# I2C_switch.net
KiCad netlist of a schematic drawn in Altium Designer
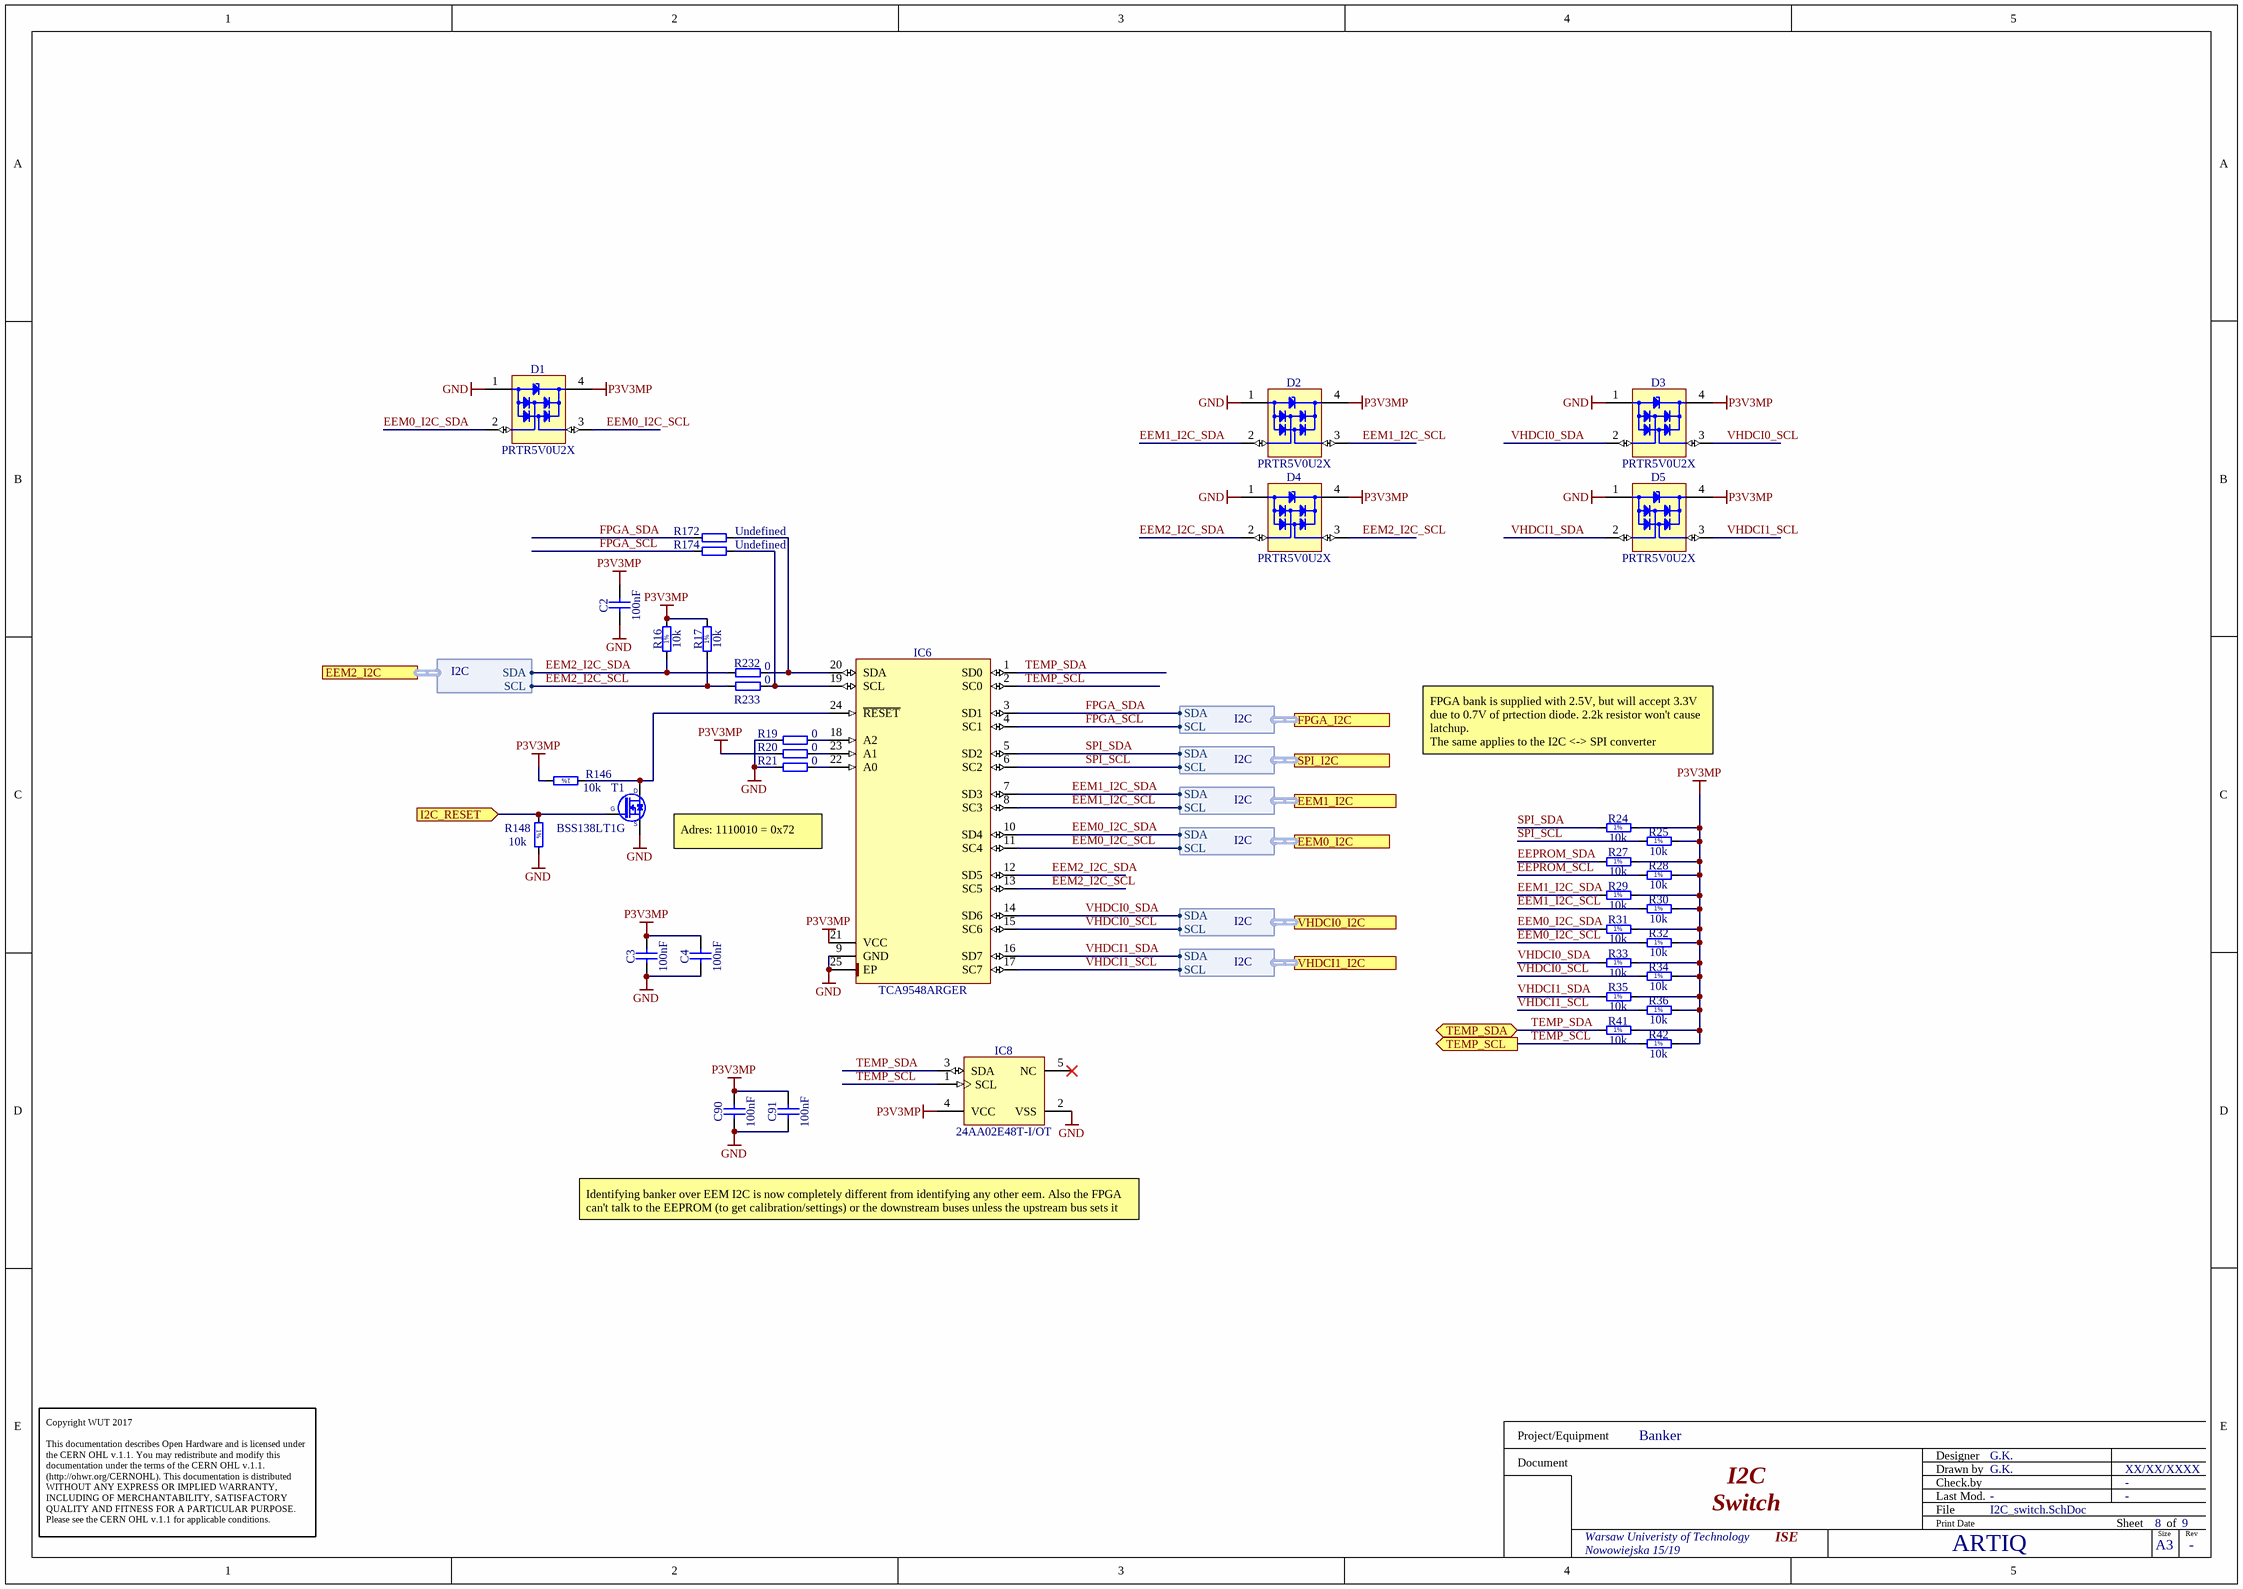
[diagram p0: I2C_switch.SchDoc]

(export (version "E")
  (design (tool "Eeschema 10.0.6"))
  (components
    (comp (ref "C2")
      (value "100nF")
      (footprint "CAPC1005X55N")
      (description "Non-polarised capacitor")
      (fields
        (field (name "PART NUMBER") "CC0402_100NF_16V_10%_X5R")
        (field (name "VOLTAGE") "16V")
        (field (name "AUTHOR") "CERN DEM JLC")
      )
      (libsource (lib "Capacitors") (part "Capacitor - non polarized"))
    )
    (comp (ref "C3")
      (value "100nF")
      (footprint "CAPC1005X55N")
      (description "Non-polarised capacitor")
      (fields
        (field (name "PART NUMBER") "CC0402_100NF_16V_10%_X5R")
        (field (name "VOLTAGE") "16V")
        (field (name "AUTHOR") "CERN DEM JLC")
      )
      (libsource (lib "Capacitors") (part "Capacitor - non polarized"))
    )
    (comp (ref "C4")
      (value "100nF")
      (footprint "CAPC1005X55N")
      (description "Non-polarised capacitor")
      (fields
        (field (name "PART NUMBER") "CC0402_100NF_16V_10%_X5R")
        (field (name "VOLTAGE") "16V")
        (field (name "AUTHOR") "CERN DEM JLC")
      )
      (libsource (lib "Capacitors") (part "Capacitor - non polarized"))
    )
    (comp (ref "C90")
      (value "100nF")
      (footprint "CAPC1005X55N")
      (description "Non-polarised capacitor")
      (fields
        (field (name "PART NUMBER") "CC0402_100NF_16V_10%_X5R")
        (field (name "VOLTAGE") "16V")
        (field (name "AUTHOR") "CERN DEM JLC")
      )
      (libsource (lib "Capacitors") (part "Capacitor - non polarized"))
    )
    (comp (ref "C91")
      (value "100nF")
      (footprint "CAPC1005X55N")
      (description "Non-polarised capacitor")
      (fields
        (field (name "PART NUMBER") "CC0402_100NF_16V_10%_X5R")
        (field (name "VOLTAGE") "16V")
        (field (name "AUTHOR") "CERN DEM JLC")
      )
      (libsource (lib "Capacitors") (part "Capacitor - non polarized"))
    )
    (comp (ref "D1")
      (value "PRTR5V0U2X")
      (footprint "SOT190P230X110-4N")
      (description "Ultra Low Capacitance Double Rail-to-Rail ESD Protection Diode")
      (fields
        (field (name "VOLTAGE") "5.5V")
        (field (name "MANUFACTURER") "NXP SEMICONDUCTORS")
        (field (name "AUTHOR") "CERN DEM JLC")
      )
      (libsource (lib "ICs And Semiconductors") (part "PRTR5V0U2X"))
    )
    (comp (ref "D2")
      (value "PRTR5V0U2X")
      (footprint "SOT190P230X110-4N")
      (description "Ultra Low Capacitance Double Rail-to-Rail ESD Protection Diode")
      (fields
        (field (name "VOLTAGE") "5.5V")
        (field (name "MANUFACTURER") "NXP SEMICONDUCTORS")
        (field (name "AUTHOR") "CERN DEM JLC")
      )
      (libsource (lib "ICs And Semiconductors") (part "PRTR5V0U2X"))
    )
    (comp (ref "D3")
      (value "PRTR5V0U2X")
      (footprint "SOT190P230X110-4N")
      (description "Ultra Low Capacitance Double Rail-to-Rail ESD Protection Diode")
      (fields
        (field (name "VOLTAGE") "5.5V")
        (field (name "MANUFACTURER") "NXP SEMICONDUCTORS")
        (field (name "AUTHOR") "CERN DEM JLC")
      )
      (libsource (lib "ICs And Semiconductors") (part "PRTR5V0U2X"))
    )
    (comp (ref "D4")
      (value "PRTR5V0U2X")
      (footprint "SOT190P230X110-4N")
      (description "Ultra Low Capacitance Double Rail-to-Rail ESD Protection Diode")
      (fields
        (field (name "VOLTAGE") "5.5V")
        (field (name "MANUFACTURER") "NXP SEMICONDUCTORS")
        (field (name "AUTHOR") "CERN DEM JLC")
      )
      (libsource (lib "ICs And Semiconductors") (part "PRTR5V0U2X"))
    )
    (comp (ref "D5")
      (value "PRTR5V0U2X")
      (footprint "SOT190P230X110-4N")
      (description "Ultra Low Capacitance Double Rail-to-Rail ESD Protection Diode")
      (fields
        (field (name "VOLTAGE") "5.5V")
        (field (name "MANUFACTURER") "NXP SEMICONDUCTORS")
        (field (name "AUTHOR") "CERN DEM JLC")
      )
      (libsource (lib "ICs And Semiconductors") (part "PRTR5V0U2X"))
    )
    (comp (ref "IC6")
      (value "TCA9548ARGER")
      (footprint "QFN50P400X400X100-25N-S220")
      (description "Low Voltage 8-Channel I2C Switch With Reset")
      (fields (field (name "MANUFACTURER") "TEXAS INSTRUMENTS") (field (name "AUTHOR") "CERN DEM JLC"))
      (libsource (lib "ICs And Semiconductors") (part "TCA9548ARGER"))
    )
    (comp (ref "IC8")
      (value "24AA02E48T-I/OT")
      (footprint "SOT95P280X145-5N")
      (description "1.7V-5.5V, 2K I2C Serial EEPROM With EUI-48 Node Identity")
      (fields (field (name "MANUFACTURER") "MICROCHIP TECHNOLOGY") (field (name "AUTHOR") "CERN DEM MR"))
      (libsource (lib "ICs And Semiconductors") (part "24AA02E48T-I/OT"))
    )
    (comp (ref "R16")
      (value "10k")
      (footprint "RESC1005X40N")
      (description "Resistor - 1%")
      (fields
        (field (name "PART NUMBER") "R0402_10K_1%_0.0625W_100PPM")
        (field (name "POWER") "0.0625W")
        (field (name "AUTHOR") "CERN DEM JLC")
      )
      (libsource (lib "Resistors") (part "Resistor - 1%"))
    )
    (comp (ref "R17")
      (value "10k")
      (footprint "RESC1005X40N")
      (description "Resistor - 1%")
      (fields
        (field (name "PART NUMBER") "R0402_10K_1%_0.0625W_100PPM")
        (field (name "POWER") "0.0625W")
        (field (name "AUTHOR") "CERN DEM JLC")
      )
      (libsource (lib "Resistors") (part "Resistor - 1%"))
    )
    (comp (ref "R19")
      (value "0")
      (footprint "RESC1005X40N")
      (description "Resistor")
      (fields
        (field (name "PART NUMBER") "R0402_0R_JUMPER")
        (field (name "MANUFACTURER") "GENERIC")
        (field (name "AUTHOR") "CERN DEM JLC")
      )
      (libsource (lib "Resistors") (part "Resistor"))
    )
    (comp (ref "R20")
      (value "0")
      (footprint "RESC1005X40N")
      (description "Resistor")
      (fields
        (field (name "PART NUMBER") "R0402_0R_JUMPER")
        (field (name "MANUFACTURER") "GENERIC")
        (field (name "AUTHOR") "CERN DEM JLC")
      )
      (libsource (lib "Resistors") (part "Resistor"))
    )
    (comp (ref "R21")
      (value "0")
      (footprint "RESC1005X40N")
      (description "Resistor")
      (fields
        (field (name "PART NUMBER") "R0402_0R_JUMPER")
        (field (name "MANUFACTURER") "GENERIC")
        (field (name "AUTHOR") "CERN DEM JLC")
      )
      (libsource (lib "Resistors") (part "Resistor"))
    )
    (comp (ref "R24")
      (value "10k")
      (footprint "RESC1005X40N")
      (description "Resistor - 1%")
      (fields
        (field (name "PART NUMBER") "R0402_10K_1%_0.0625W_100PPM")
        (field (name "POWER") "0.0625W")
        (field (name "AUTHOR") "CERN DEM JLC")
      )
      (libsource (lib "Resistors") (part "Resistor - 1%"))
    )
    (comp (ref "R25")
      (value "10k")
      (footprint "RESC1005X40N")
      (description "Resistor - 1%")
      (fields
        (field (name "PART NUMBER") "R0402_10K_1%_0.0625W_100PPM")
        (field (name "POWER") "0.0625W")
        (field (name "AUTHOR") "CERN DEM JLC")
      )
      (libsource (lib "Resistors") (part "Resistor - 1%"))
    )
    (comp (ref "R27")
      (value "10k")
      (footprint "RESC1005X40N")
      (description "Resistor - 1%")
      (fields
        (field (name "PART NUMBER") "R0402_10K_1%_0.0625W_100PPM")
        (field (name "POWER") "0.0625W")
        (field (name "AUTHOR") "CERN DEM JLC")
      )
      (libsource (lib "Resistors") (part "Resistor - 1%"))
    )
    (comp (ref "R28")
      (value "10k")
      (footprint "RESC1005X40N")
      (description "Resistor - 1%")
      (fields
        (field (name "PART NUMBER") "R0402_10K_1%_0.0625W_100PPM")
        (field (name "POWER") "0.0625W")
        (field (name "AUTHOR") "CERN DEM JLC")
      )
      (libsource (lib "Resistors") (part "Resistor - 1%"))
    )
    (comp (ref "R29")
      (value "10k")
      (footprint "RESC1005X40N")
      (description "Resistor - 1%")
      (fields
        (field (name "PART NUMBER") "R0402_10K_1%_0.0625W_100PPM")
        (field (name "POWER") "0.0625W")
        (field (name "AUTHOR") "CERN DEM JLC")
      )
      (libsource (lib "Resistors") (part "Resistor - 1%"))
    )
    (comp (ref "R30")
      (value "10k")
      (footprint "RESC1005X40N")
      (description "Resistor - 1%")
      (fields
        (field (name "PART NUMBER") "R0402_10K_1%_0.0625W_100PPM")
        (field (name "POWER") "0.0625W")
        (field (name "AUTHOR") "CERN DEM JLC")
      )
      (libsource (lib "Resistors") (part "Resistor - 1%"))
    )
    (comp (ref "R31")
      (value "10k")
      (footprint "RESC1005X40N")
      (description "Resistor - 1%")
      (fields
        (field (name "PART NUMBER") "R0402_10K_1%_0.0625W_100PPM")
        (field (name "POWER") "0.0625W")
        (field (name "AUTHOR") "CERN DEM JLC")
      )
      (libsource (lib "Resistors") (part "Resistor - 1%"))
    )
    (comp (ref "R32")
      (value "10k")
      (footprint "RESC1005X40N")
      (description "Resistor - 1%")
      (fields
        (field (name "PART NUMBER") "R0402_10K_1%_0.0625W_100PPM")
        (field (name "POWER") "0.0625W")
        (field (name "AUTHOR") "CERN DEM JLC")
      )
      (libsource (lib "Resistors") (part "Resistor - 1%"))
    )
    (comp (ref "R33")
      (value "10k")
      (footprint "RESC1005X40N")
      (description "Resistor - 1%")
      (fields
        (field (name "PART NUMBER") "R0402_10K_1%_0.0625W_100PPM")
        (field (name "POWER") "0.0625W")
        (field (name "AUTHOR") "CERN DEM JLC")
      )
      (libsource (lib "Resistors") (part "Resistor - 1%"))
    )
    (comp (ref "R34")
      (value "10k")
      (footprint "RESC1005X40N")
      (description "Resistor - 1%")
      (fields
        (field (name "PART NUMBER") "R0402_10K_1%_0.0625W_100PPM")
        (field (name "POWER") "0.0625W")
        (field (name "AUTHOR") "CERN DEM JLC")
      )
      (libsource (lib "Resistors") (part "Resistor - 1%"))
    )
    (comp (ref "R35")
      (value "10k")
      (footprint "RESC1005X40N")
      (description "Resistor - 1%")
      (fields
        (field (name "PART NUMBER") "R0402_10K_1%_0.0625W_100PPM")
        (field (name "POWER") "0.0625W")
        (field (name "AUTHOR") "CERN DEM JLC")
      )
      (libsource (lib "Resistors") (part "Resistor - 1%"))
    )
    (comp (ref "R36")
      (value "10k")
      (footprint "RESC1005X40N")
      (description "Resistor - 1%")
      (fields
        (field (name "PART NUMBER") "R0402_10K_1%_0.0625W_100PPM")
        (field (name "POWER") "0.0625W")
        (field (name "AUTHOR") "CERN DEM JLC")
      )
      (libsource (lib "Resistors") (part "Resistor - 1%"))
    )
    (comp (ref "R41")
      (value "10k")
      (footprint "RESC1005X40N")
      (description "Resistor - 1%")
      (fields
        (field (name "PART NUMBER") "R0402_10K_1%_0.0625W_100PPM")
        (field (name "POWER") "0.0625W")
        (field (name "AUTHOR") "CERN DEM JLC")
      )
      (libsource (lib "Resistors") (part "Resistor - 1%"))
    )
    (comp (ref "R42")
      (value "10k")
      (footprint "RESC1005X40N")
      (description "Resistor - 1%")
      (fields
        (field (name "PART NUMBER") "R0402_10K_1%_0.0625W_100PPM")
        (field (name "POWER") "0.0625W")
        (field (name "AUTHOR") "CERN DEM JLC")
      )
      (libsource (lib "Resistors") (part "Resistor - 1%"))
    )
    (comp (ref "R146")
      (value "10k")
      (footprint "RESC1005X40N")
      (description "Resistor - 1%")
      (fields
        (field (name "PART NUMBER") "R0402_10K_1%_0.0625W_100PPM")
        (field (name "POWER") "0.0625W")
        (field (name "AUTHOR") "CERN DEM JLC")
      )
      (libsource (lib "Resistors") (part "Resistor - 1%"))
    )
    (comp (ref "R148")
      (value "10k")
      (footprint "RESC1005X40N")
      (description "Resistor - 1%")
      (fields
        (field (name "PART NUMBER") "R0402_10K_1%_0.0625W_100PPM")
        (field (name "POWER") "0.0625W")
        (field (name "AUTHOR") "CERN DEM JLC")
      )
      (libsource (lib "Resistors") (part "Resistor - 1%"))
    )
    (comp (ref "R172")
      (value "Undefined")
      (footprint "RESC1608X55N")
      (description "Resistor")
      (fields (field (name "PART NUMBER") "R0603_NO-VALUE") (field (name "AUTHOR") "CERN DEM JLC"))
      (libsource (lib "Resistors") (part "Resistor"))
    )
    (comp (ref "R174")
      (value "Undefined")
      (footprint "RESC1608X55N")
      (description "Resistor")
      (fields (field (name "PART NUMBER") "R0603_NO-VALUE") (field (name "AUTHOR") "CERN DEM JLC"))
      (libsource (lib "Resistors") (part "Resistor"))
    )
    (comp (ref "R232")
      (value "0")
      (footprint "RESC1608X55N")
      (description "Resistor")
      (fields
        (field (name "PART NUMBER") "R0603_0R_JUMPER")
        (field (name "MANUFACTURER") "GENERIC")
        (field (name "AUTHOR") "CERN DEM JLC")
      )
      (libsource (lib "Resistors") (part "Resistor"))
    )
    (comp (ref "R233")
      (value "0")
      (footprint "RESC1608X55N")
      (description "Resistor")
      (fields
        (field (name "PART NUMBER") "R0603_0R_JUMPER")
        (field (name "MANUFACTURER") "GENERIC")
        (field (name "AUTHOR") "CERN DEM JLC")
      )
      (libsource (lib "Resistors") (part "Resistor"))
    )
    (comp (ref "T1")
      (value "BSS138LT1G")
      (footprint "SOT95P240X110-3N")
      (description "N-CHANNEL MOSFET WITH DIODE")
      (fields (field (name "MANUFACTURER") "ON SEMICONDUCTOR") (field (name "AUTHOR") "CERN DEM JLC"))
      (libsource (lib "ICs And Semiconductors") (part "N-MOSFET-D 1G 2S 3D"))
    )
  )
  (nets
    (net (code "2") (name "/EEM0_I2C_SCL") (class "Default")
      (node (ref "D1") (pin "3") (pinfunction "I/O2_3") (pintype "bidirectional"))
      (node (ref "IC6") (pin "11") (pinfunction "SC4_11") (pintype "bidirectional"))
      (node (ref "R32") (pin "1") (pinfunction "1_1") (pintype "passive"))
    )
    (net (code "3") (name "/EEM0_I2C_SDA") (class "Default")
      (node (ref "D1") (pin "2") (pinfunction "I/O1_2") (pintype "bidirectional"))
      (node (ref "IC6") (pin "10") (pinfunction "SD4_10") (pintype "bidirectional"))
      (node (ref "R31") (pin "1") (pinfunction "1_1") (pintype "passive"))
    )
    (net (code "4") (name "/EEM1_I2C_SCL") (class "Default")
      (node (ref "D2") (pin "3") (pinfunction "I/O2_3") (pintype "bidirectional"))
      (node (ref "IC6") (pin "8") (pinfunction "SC3_8") (pintype "bidirectional"))
      (node (ref "R30") (pin "1") (pinfunction "1_1") (pintype "passive"))
    )
    (net (code "5") (name "/EEM1_I2C_SDA") (class "Default")
      (node (ref "D2") (pin "2") (pinfunction "I/O1_2") (pintype "bidirectional"))
      (node (ref "IC6") (pin "7") (pinfunction "SD3_7") (pintype "bidirectional"))
      (node (ref "R29") (pin "1") (pinfunction "1_1") (pintype "passive"))
    )
    (net (code "6") (name "/EEM2_I2C_SCL") (class "Default")
      (node (ref "D4") (pin "3") (pinfunction "I/O2_3") (pintype "bidirectional"))
      (node (ref "IC6") (pin "13") (pinfunction "SC5_13") (pintype "bidirectional"))
      (node (ref "R17") (pin "1") (pinfunction "1_1") (pintype "passive"))
      (node (ref "R233") (pin "1") (pinfunction "1_1") (pintype "passive"))
    )
    (net (code "7") (name "/EEM2_I2C_SDA") (class "Default")
      (node (ref "D4") (pin "2") (pinfunction "I/O1_2") (pintype "bidirectional"))
      (node (ref "IC6") (pin "12") (pinfunction "SD5_12") (pintype "bidirectional"))
      (node (ref "R16") (pin "1") (pinfunction "1_1") (pintype "passive"))
      (node (ref "R232") (pin "1") (pinfunction "1_1") (pintype "passive"))
    )
    (net (code "8") (name "/EEPROM_SCL") (class "Default")
      (node (ref "R28") (pin "1") (pinfunction "1_1") (pintype "passive"))
    )
    (net (code "9") (name "/EEPROM_SDA") (class "Default")
      (node (ref "R27") (pin "1") (pinfunction "1_1") (pintype "passive"))
    )
    (net (code "10") (name "/FPGA_SCL") (class "Default")
      (node (ref "IC6") (pin "4") (pinfunction "SC1_4") (pintype "bidirectional"))
      (node (ref "R174") (pin "1") (pinfunction "1_1") (pintype "passive"))
    )
    (net (code "11") (name "/FPGA_SDA") (class "Default")
      (node (ref "IC6") (pin "3") (pinfunction "SD1_3") (pintype "bidirectional"))
      (node (ref "R172") (pin "1") (pinfunction "1_1") (pintype "passive"))
    )
    (net (code "12") (name "/I2C_RESET") (class "Default")
      (node (ref "R148") (pin "1") (pinfunction "1_1") (pintype "passive"))
      (node (ref "T1") (pin "1") (pinfunction "G_1") (pintype "passive"))
    )
    (net (code "13") (name "/SPI_SCL") (class "Default")
      (node (ref "IC6") (pin "6") (pinfunction "SC2_6") (pintype "bidirectional"))
      (node (ref "R25") (pin "1") (pinfunction "1_1") (pintype "passive"))
    )
    (net (code "14") (name "/SPI_SDA") (class "Default")
      (node (ref "IC6") (pin "5") (pinfunction "SD2_5") (pintype "bidirectional"))
      (node (ref "R24") (pin "1") (pinfunction "1_1") (pintype "passive"))
    )
    (net (code "15") (name "/TEMP_SCL") (class "Default")
      (node (ref "IC6") (pin "2") (pinfunction "SC0_2") (pintype "bidirectional"))
      (node (ref "IC8") (pin "1") (pinfunction "SCL_1") (pintype "input"))
      (node (ref "R42") (pin "1") (pinfunction "1_1") (pintype "passive"))
    )
    (net (code "16") (name "/TEMP_SDA") (class "Default")
      (node (ref "IC6") (pin "1") (pinfunction "SD0_1") (pintype "bidirectional"))
      (node (ref "IC8") (pin "3") (pinfunction "SDA_3") (pintype "bidirectional"))
      (node (ref "R41") (pin "1") (pinfunction "1_1") (pintype "passive"))
    )
    (net (code "17") (name "/VHDCI0_SCL") (class "Default")
      (node (ref "D3") (pin "3") (pinfunction "I/O2_3") (pintype "bidirectional"))
      (node (ref "IC6") (pin "15") (pinfunction "SC6_15") (pintype "bidirectional"))
      (node (ref "R34") (pin "1") (pinfunction "1_1") (pintype "passive"))
    )
    (net (code "18") (name "/VHDCI0_SDA") (class "Default")
      (node (ref "D3") (pin "2") (pinfunction "I/O1_2") (pintype "bidirectional"))
      (node (ref "IC6") (pin "14") (pinfunction "SD6_14") (pintype "bidirectional"))
      (node (ref "R33") (pin "1") (pinfunction "1_1") (pintype "passive"))
    )
    (net (code "19") (name "/VHDCI1_SCL") (class "Default")
      (node (ref "D5") (pin "3") (pinfunction "I/O2_3") (pintype "bidirectional"))
      (node (ref "IC6") (pin "17") (pinfunction "SC7_17") (pintype "bidirectional"))
      (node (ref "R36") (pin "1") (pinfunction "1_1") (pintype "passive"))
    )
    (net (code "20") (name "/VHDCI1_SDA") (class "Default")
      (node (ref "D5") (pin "2") (pinfunction "I/O1_2") (pintype "bidirectional"))
      (node (ref "IC6") (pin "16") (pinfunction "SD7_16") (pintype "bidirectional"))
      (node (ref "R35") (pin "1") (pinfunction "1_1") (pintype "passive"))
    )
    (net (code "22") (name "GND") (class "Default")
      (node (ref "C2") (pin "1") (pinfunction "1_1") (pintype "passive"))
      (node (ref "C3") (pin "1") (pinfunction "1_1") (pintype "passive"))
      (node (ref "C4") (pin "1") (pinfunction "1_1") (pintype "passive"))
      (node (ref "C90") (pin "1") (pinfunction "1_1") (pintype "passive"))
      (node (ref "C91") (pin "1") (pinfunction "1_1") (pintype "passive"))
      (node (ref "D1") (pin "1") (pinfunction "GND_1") (pintype "power_in"))
      (node (ref "D2") (pin "1") (pinfunction "GND_1") (pintype "power_in"))
      (node (ref "D3") (pin "1") (pinfunction "GND_1") (pintype "power_in"))
      (node (ref "D4") (pin "1") (pinfunction "GND_1") (pintype "power_in"))
      (node (ref "D5") (pin "1") (pinfunction "GND_1") (pintype "power_in"))
      (node (ref "IC6") (pin "25") (pinfunction "EP_25") (pintype "power_in"))
      (node (ref "IC6") (pin "9") (pinfunction "GND_9") (pintype "power_in"))
      (node (ref "IC8") (pin "2") (pinfunction "VSS_2") (pintype "power_in"))
      (node (ref "R148") (pin "2") (pinfunction "2_2") (pintype "passive"))
      (node (ref "R19") (pin "1") (pinfunction "1_1") (pintype "passive"))
      (node (ref "R21") (pin "1") (pinfunction "1_1") (pintype "passive"))
      (node (ref "T1") (pin "2") (pinfunction "S_2") (pintype "passive"))
    )
    (net (code "23") (name "Net-(IC6-A0)") (class "Default")
      (node (ref "IC6") (pin "22") (pinfunction "A0_22") (pintype "input"))
      (node (ref "R21") (pin "2") (pinfunction "2_2") (pintype "passive"))
    )
    (net (code "24") (name "Net-(IC6-A1)") (class "Default")
      (node (ref "IC6") (pin "23") (pinfunction "A1_23") (pintype "input"))
      (node (ref "R20") (pin "2") (pinfunction "2_2") (pintype "passive"))
    )
    (net (code "25") (name "Net-(IC6-A2)") (class "Default")
      (node (ref "IC6") (pin "18") (pinfunction "A2_18") (pintype "input"))
      (node (ref "R19") (pin "2") (pinfunction "2_2") (pintype "passive"))
    )
    (net (code "26") (name "Net-(IC6-SCL)") (class "Default")
      (node (ref "IC6") (pin "19") (pinfunction "SCL_19") (pintype "bidirectional"))
      (node (ref "R174") (pin "2") (pinfunction "2_2") (pintype "passive"))
      (node (ref "R233") (pin "2") (pinfunction "2_2") (pintype "passive"))
    )
    (net (code "27") (name "Net-(IC6-SDA)") (class "Default")
      (node (ref "IC6") (pin "20") (pinfunction "SDA_20") (pintype "bidirectional"))
      (node (ref "R172") (pin "2") (pinfunction "2_2") (pintype "passive"))
      (node (ref "R232") (pin "2") (pinfunction "2_2") (pintype "passive"))
    )
    (net (code "28") (name "Net-(IC6-~{RESET})") (class "Default")
      (node (ref "IC6") (pin "24") (pinfunction "~{RESET}_24") (pintype "input"))
      (node (ref "R146") (pin "1") (pinfunction "1_1") (pintype "passive"))
      (node (ref "T1") (pin "3") (pinfunction "D_3") (pintype "passive"))
    )
    (net (code "29") (name "P3V3MP") (class "Default")
      (node (ref "C2") (pin "2") (pinfunction "2_2") (pintype "passive"))
      (node (ref "C3") (pin "2") (pinfunction "2_2") (pintype "passive"))
      (node (ref "C4") (pin "2") (pinfunction "2_2") (pintype "passive"))
      (node (ref "C90") (pin "2") (pinfunction "2_2") (pintype "passive"))
      (node (ref "C91") (pin "2") (pinfunction "2_2") (pintype "passive"))
      (node (ref "D1") (pin "4") (pinfunction "VCC_4") (pintype "power_in"))
      (node (ref "D2") (pin "4") (pinfunction "VCC_4") (pintype "power_in"))
      (node (ref "D3") (pin "4") (pinfunction "VCC_4") (pintype "power_in"))
      (node (ref "D4") (pin "4") (pinfunction "VCC_4") (pintype "power_in"))
      (node (ref "D5") (pin "4") (pinfunction "VCC_4") (pintype "power_in"))
      (node (ref "IC6") (pin "21") (pinfunction "VCC_21") (pintype "power_in"))
      (node (ref "IC8") (pin "4") (pinfunction "VCC_4") (pintype "power_in"))
      (node (ref "R146") (pin "2") (pinfunction "2_2") (pintype "passive"))
      (node (ref "R16") (pin "2") (pinfunction "2_2") (pintype "passive"))
      (node (ref "R17") (pin "2") (pinfunction "2_2") (pintype "passive"))
      (node (ref "R20") (pin "1") (pinfunction "1_1") (pintype "passive"))
      (node (ref "R24") (pin "2") (pinfunction "2_2") (pintype "passive"))
      (node (ref "R25") (pin "2") (pinfunction "2_2") (pintype "passive"))
      (node (ref "R27") (pin "2") (pinfunction "2_2") (pintype "passive"))
      (node (ref "R28") (pin "2") (pinfunction "2_2") (pintype "passive"))
      (node (ref "R29") (pin "2") (pinfunction "2_2") (pintype "passive"))
      (node (ref "R30") (pin "2") (pinfunction "2_2") (pintype "passive"))
      (node (ref "R31") (pin "2") (pinfunction "2_2") (pintype "passive"))
      (node (ref "R32") (pin "2") (pinfunction "2_2") (pintype "passive"))
      (node (ref "R33") (pin "2") (pinfunction "2_2") (pintype "passive"))
      (node (ref "R34") (pin "2") (pinfunction "2_2") (pintype "passive"))
      (node (ref "R35") (pin "2") (pinfunction "2_2") (pintype "passive"))
      (node (ref "R36") (pin "2") (pinfunction "2_2") (pintype "passive"))
      (node (ref "R41") (pin "2") (pinfunction "2_2") (pintype "passive"))
      (node (ref "R42") (pin "2") (pinfunction "2_2") (pintype "passive"))
    )
    (net (code "30") (name "unconnected-(IC8-NC-Pad5)") (class "Default")
      (node (ref "IC8") (pin "5") (pinfunction "NC_5") (pintype "passive+no_connect"))
    )
  )
)
